# MAX3232_Breakout.net
KiCad netlist of a schematic drawn in EAGLE
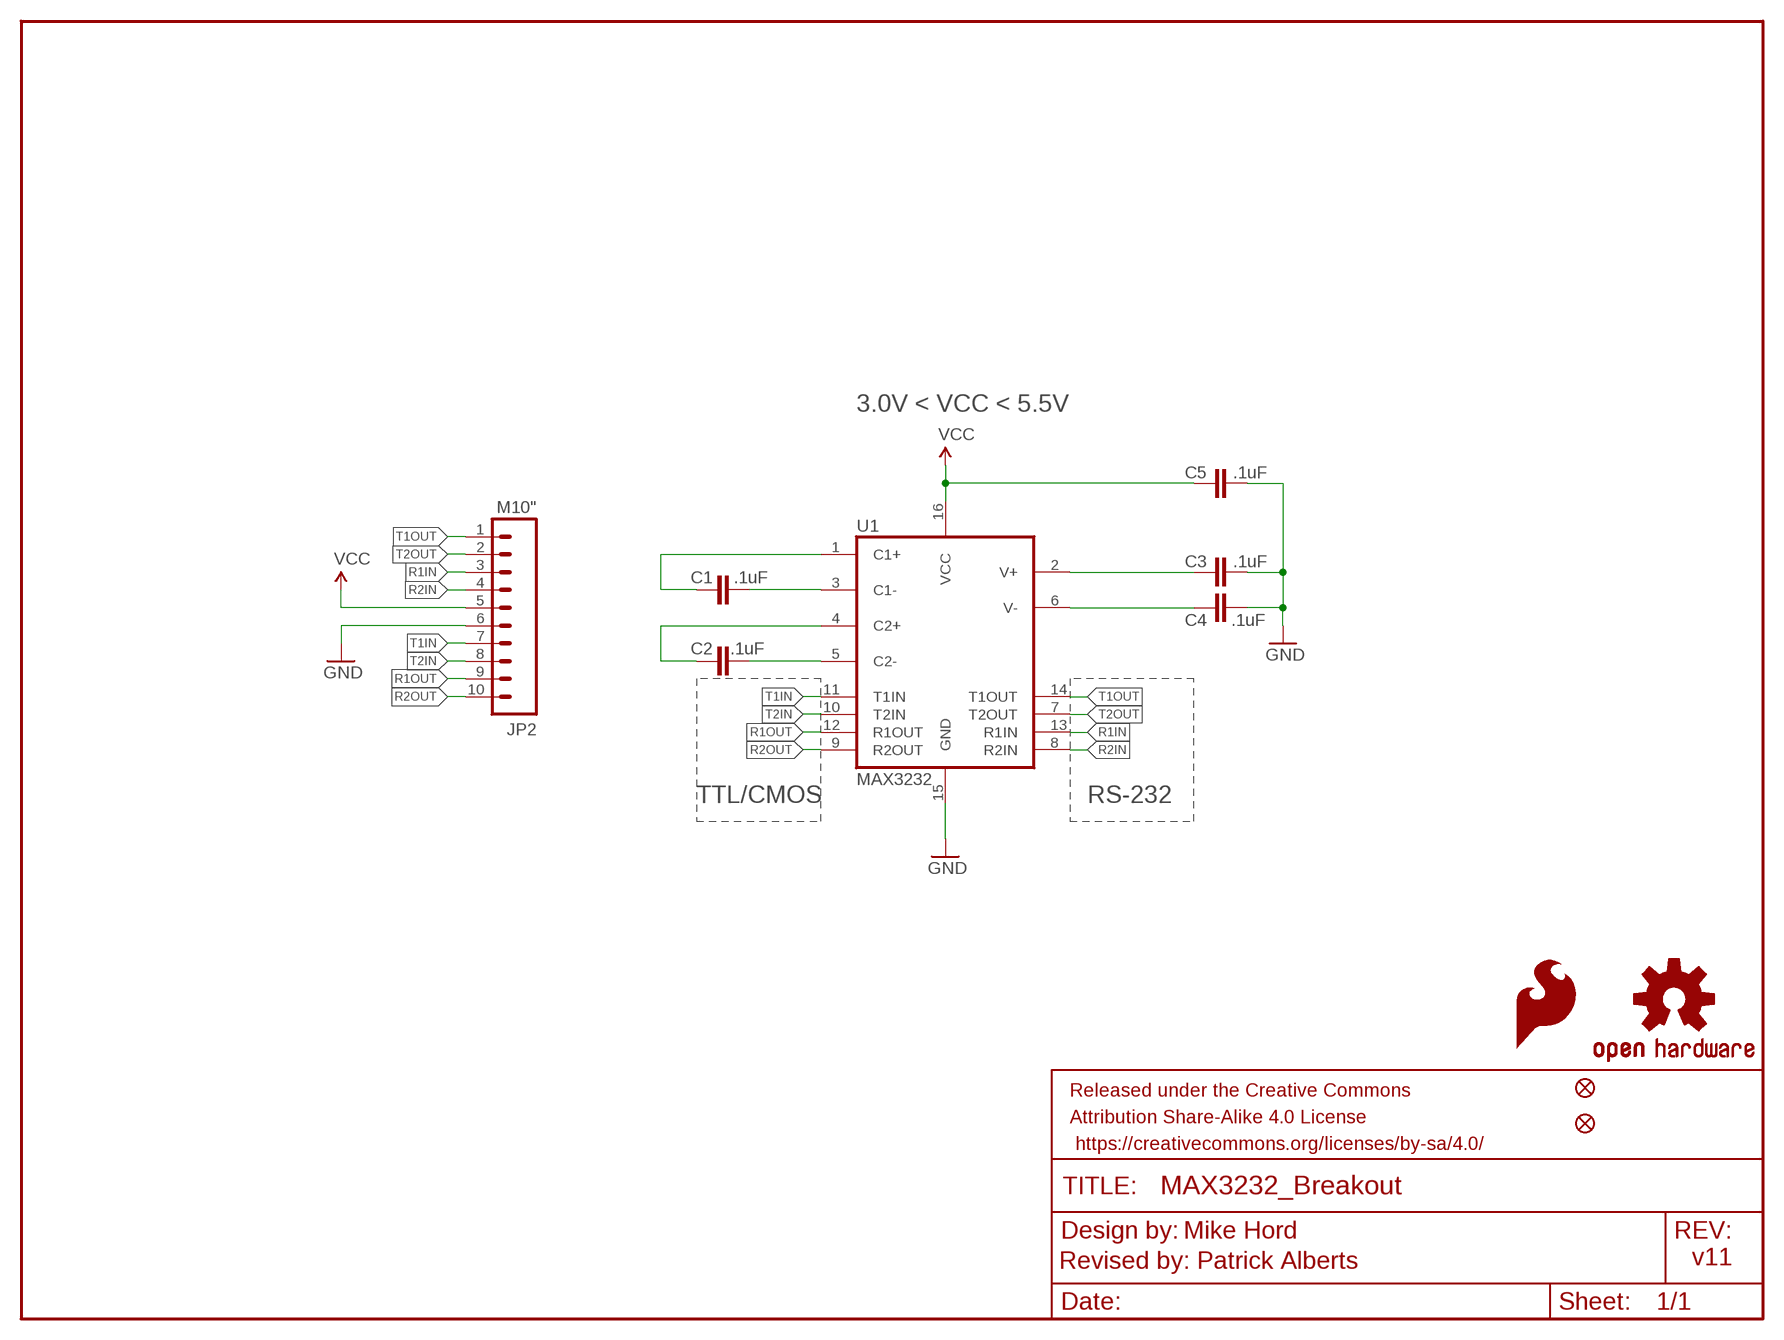
[diagram p0: schematic, sheet 1]

(export (version "E")
  (design (tool "Eeschema 10.0.6"))
  (components
    (comp (ref "C1")
      (value ".1uF")
      (footprint "eagle-import:0603-CAP")
      (fields (field (name "PROD_ID") "CAP-00810"))
      (libsource (lib "eagle-import") (part "0.1UF-25V(+80/-20%)(0603)"))
    )
    (comp (ref "C2")
      (value ".1uF")
      (footprint "eagle-import:0603-CAP")
      (fields (field (name "PROD_ID") "CAP-00810"))
      (libsource (lib "eagle-import") (part "0.1UF-25V(+80/-20%)(0603)"))
    )
    (comp (ref "C3")
      (value ".1uF")
      (footprint "eagle-import:0603-CAP")
      (fields (field (name "PROD_ID") "CAP-00810"))
      (libsource (lib "eagle-import") (part "0.1UF-25V(+80/-20%)(0603)"))
    )
    (comp (ref "C4")
      (value ".1uF")
      (footprint "eagle-import:0603-CAP")
      (fields (field (name "PROD_ID") "CAP-00810"))
      (libsource (lib "eagle-import") (part "0.1UF-25V(+80/-20%)(0603)"))
    )
    (comp (ref "C5")
      (value ".1uF")
      (footprint "eagle-import:0603-CAP")
      (fields (field (name "PROD_ID") "CAP-00810"))
      (libsource (lib "eagle-import") (part "0.1UF-25V(+80/-20%)(0603)"))
    )
    (comp (ref "FRAME1")
      (value "FRAME-LETTER")
      (footprint "eagle-import:CREATIVE_COMMONS")
      (fields (field (name "NO_PART") "1") (field (name "DESIGNER") "NAME"))
      (libsource (lib "eagle-import") (part "FRAME-LETTER"))
    )
    (comp (ref "JP2")
      (value "M10\"")
      (footprint "eagle-import:1X10")
      (fields (field (name "NO_PART") "1"))
      (libsource (lib "eagle-import") (part "M10{dblquote}"))
    )
    (comp (ref "JP3")
      (value "FIDUCIALUFIDUCIAL")
      (footprint "eagle-import:MICRO-FIDUCIAL")
      (libsource (lib "eagle-import") (part "FIDUCIALUFIDUCIAL"))
    )
    (comp (ref "JP4")
      (value "FIDUCIALUFIDUCIAL")
      (footprint "eagle-import:MICRO-FIDUCIAL")
      (libsource (lib "eagle-import") (part "FIDUCIALUFIDUCIAL"))
    )
    (comp (ref "LOGO1")
      (value "SFE_LOGO_FLAME.1_INCH")
      (footprint "eagle-import:SFE_LOGO_FLAME_.1")
      (libsource (lib "eagle-import") (part "SFE_LOGO_FLAME.1_INCH"))
    )
    (comp (ref "U$1")
      (value "OSHW-LOGOS")
      (footprint "eagle-import:OSHW-LOGO-S")
      (fields (field (name "NO_PART") "1"))
      (libsource (lib "eagle-import") (part "OSHW-LOGOS"))
    )
    (comp (ref "U1")
      (value "MAX3232")
      (footprint "eagle-import:SO016")
      (libsource (lib "eagle-import") (part "MAX232SOIC16"))
    )
  )
  (nets
    (net (code "1") (name "GND") (class "Default")
      (node (ref "C3") (pin "2") (pinfunction "2_2") (pintype "passive"))
      (node (ref "C4") (pin "2") (pinfunction "2_2") (pintype "passive"))
      (node (ref "C5") (pin "2") (pinfunction "2_2") (pintype "passive"))
      (node (ref "JP2") (pin "6") (pinfunction "6_6") (pintype "passive"))
      (node (ref "U1") (pin "15") (pinfunction "GND_15") (pintype "bidirectional"))
    )
    (net (code "2") (name "Net-(U1-C1+)") (class "Default")
      (node (ref "C1") (pin "1") (pinfunction "1_1") (pintype "passive"))
      (node (ref "U1") (pin "1") (pinfunction "C1+_1") (pintype "bidirectional"))
    )
    (net (code "3") (name "Net-(U1-C1-)") (class "Default")
      (node (ref "C1") (pin "2") (pinfunction "2_2") (pintype "passive"))
      (node (ref "U1") (pin "3") (pinfunction "C1-_3") (pintype "bidirectional"))
    )
    (net (code "4") (name "Net-(U1-C2+)") (class "Default")
      (node (ref "C2") (pin "1") (pinfunction "1_1") (pintype "passive"))
      (node (ref "U1") (pin "4") (pinfunction "C2+_4") (pintype "bidirectional"))
    )
    (net (code "5") (name "Net-(U1-C2-)") (class "Default")
      (node (ref "C2") (pin "2") (pinfunction "2_2") (pintype "passive"))
      (node (ref "U1") (pin "5") (pinfunction "C2-_5") (pintype "bidirectional"))
    )
    (net (code "6") (name "Net-(U1-V+)") (class "Default")
      (node (ref "C3") (pin "1") (pinfunction "1_1") (pintype "passive"))
      (node (ref "U1") (pin "2") (pinfunction "V+_2") (pintype "bidirectional"))
    )
    (net (code "7") (name "Net-(U1-V-)") (class "Default")
      (node (ref "C4") (pin "1") (pinfunction "1_1") (pintype "passive"))
      (node (ref "U1") (pin "6") (pinfunction "V-_6") (pintype "bidirectional"))
    )
    (net (code "8") (name "R1IN") (class "Default")
      (node (ref "JP2") (pin "3") (pinfunction "3_3") (pintype "passive"))
      (node (ref "U1") (pin "13") (pinfunction "R1IN_13") (pintype "input"))
    )
    (net (code "9") (name "R1OUT") (class "Default")
      (node (ref "JP2") (pin "9") (pinfunction "9_9") (pintype "passive"))
      (node (ref "U1") (pin "12") (pinfunction "R1OUT_12") (pintype "output"))
    )
    (net (code "10") (name "R2IN") (class "Default")
      (node (ref "JP2") (pin "4") (pinfunction "4_4") (pintype "passive"))
      (node (ref "U1") (pin "8") (pinfunction "R2IN_8") (pintype "input"))
    )
    (net (code "11") (name "R2OUT") (class "Default")
      (node (ref "JP2") (pin "10") (pinfunction "10_10") (pintype "passive"))
      (node (ref "U1") (pin "9") (pinfunction "R2OUT_9") (pintype "output"))
    )
    (net (code "12") (name "T1IN") (class "Default")
      (node (ref "JP2") (pin "7") (pinfunction "7_7") (pintype "passive"))
      (node (ref "U1") (pin "11") (pinfunction "T1IN_11") (pintype "input"))
    )
    (net (code "13") (name "T1OUT") (class "Default")
      (node (ref "JP2") (pin "1") (pinfunction "1_1") (pintype "passive"))
      (node (ref "U1") (pin "14") (pinfunction "T1OUT_14") (pintype "output"))
    )
    (net (code "14") (name "T2IN") (class "Default")
      (node (ref "JP2") (pin "8") (pinfunction "8_8") (pintype "passive"))
      (node (ref "U1") (pin "10") (pinfunction "T2IN_10") (pintype "input"))
    )
    (net (code "15") (name "T2OUT") (class "Default")
      (node (ref "JP2") (pin "2") (pinfunction "2_2") (pintype "passive"))
      (node (ref "U1") (pin "7") (pinfunction "T2OUT_7") (pintype "output"))
    )
    (net (code "16") (name "VCC") (class "Default")
      (node (ref "C5") (pin "1") (pinfunction "1_1") (pintype "passive"))
      (node (ref "JP2") (pin "5") (pinfunction "5_5") (pintype "passive"))
      (node (ref "U1") (pin "16") (pinfunction "VCC_16") (pintype "bidirectional"))
    )
  )
)
